# schematic.net
KiCad netlist of a schematic drawn in EAGLE
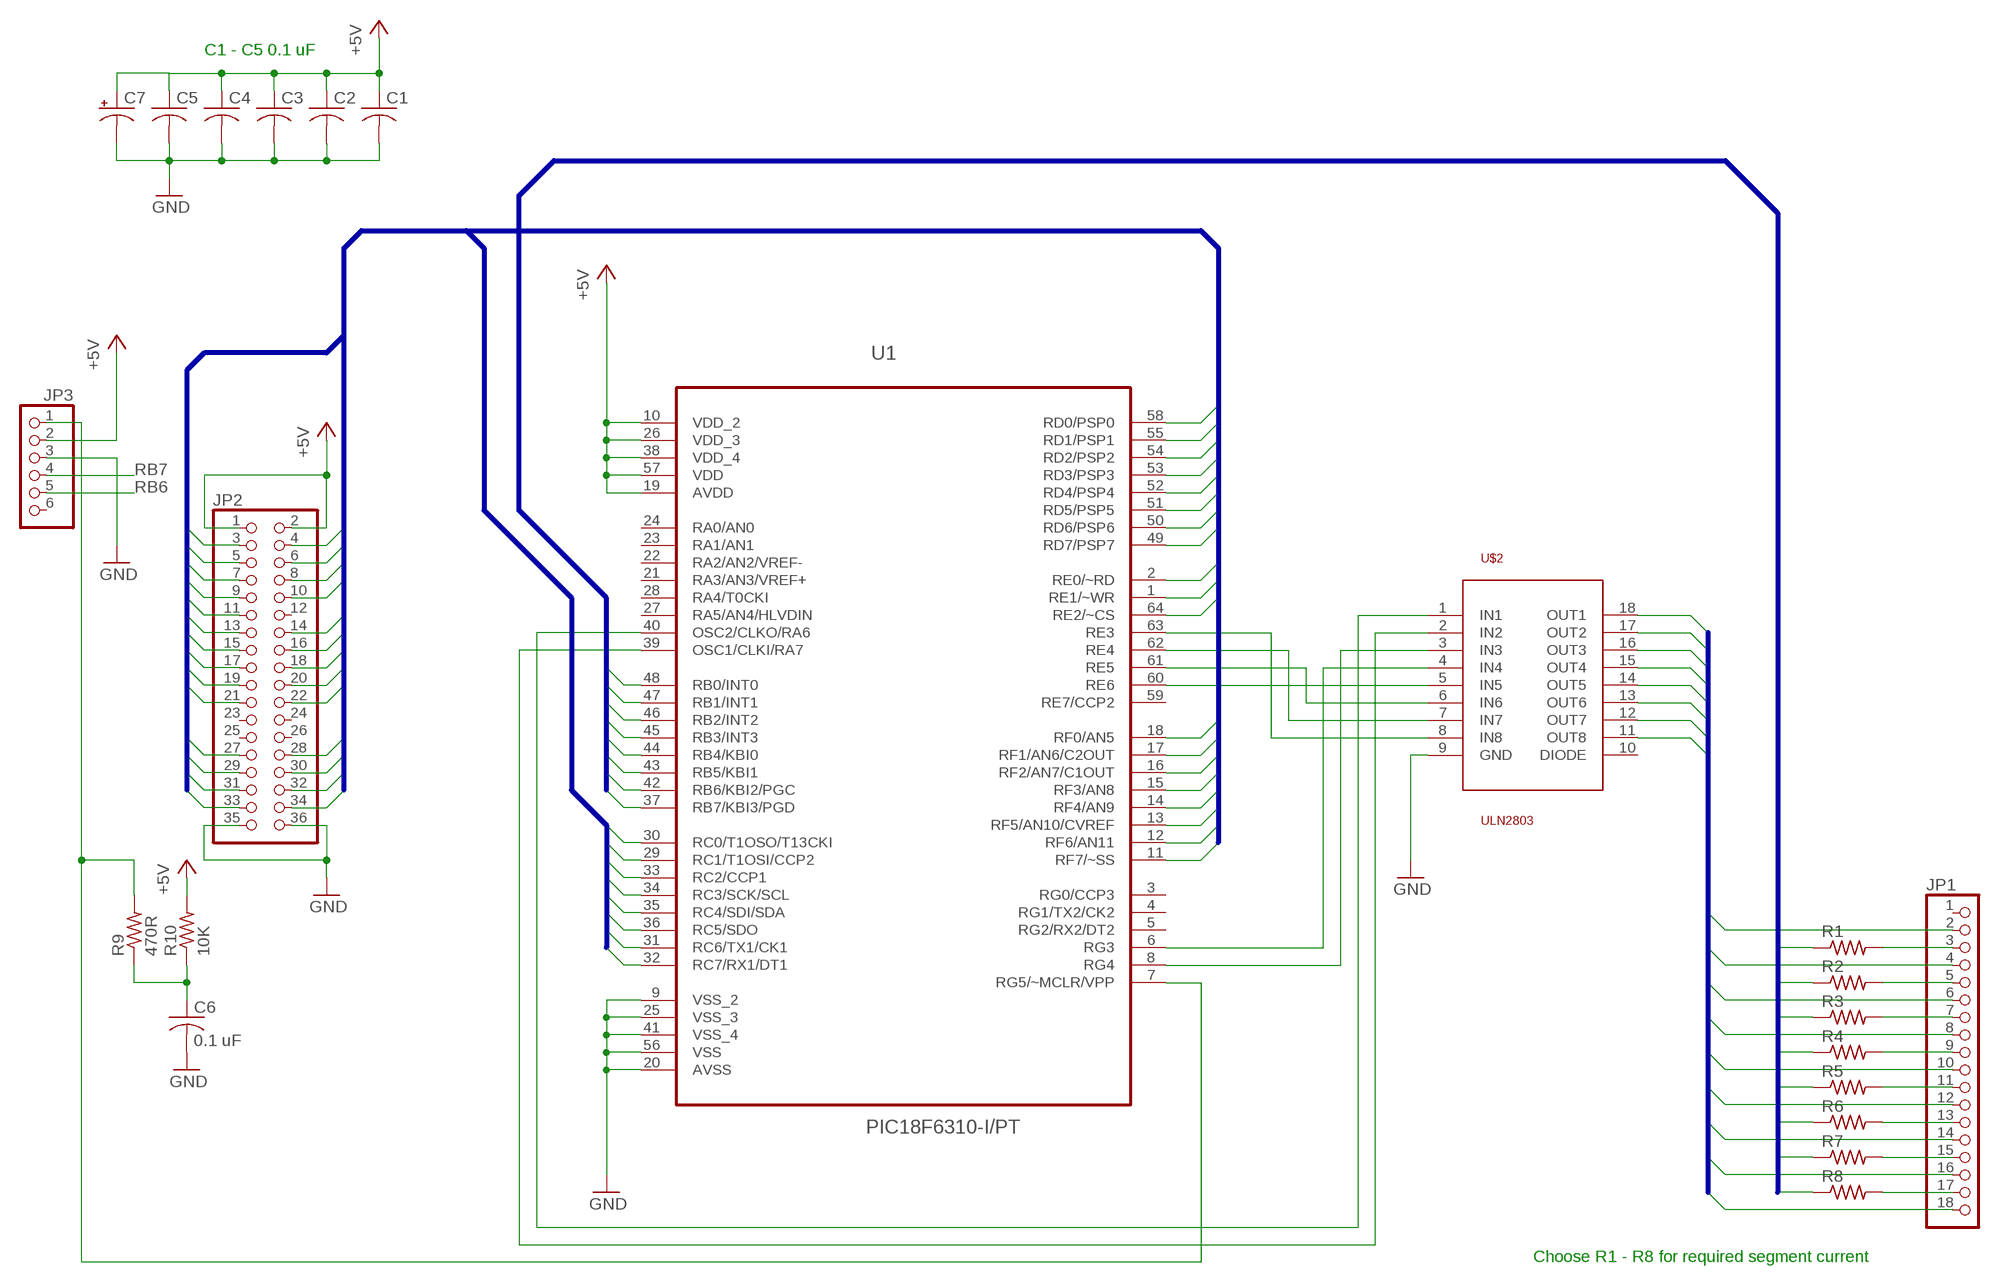
[diagram p0: schematic, sheet 1]

(export (version "E")
  (design (tool "Eeschema 10.0.6"))
  (components
    (comp (ref "C1")
      (value "C-USC0603K")
      (footprint "eagle-import:C0603K")
      (libsource (lib "eagle-import") (part "C-USC0603K"))
    )
    (comp (ref "C2")
      (value "C-USC0603K")
      (footprint "eagle-import:C0603K")
      (libsource (lib "eagle-import") (part "C-USC0603K"))
    )
    (comp (ref "C3")
      (value "C-USC0603K")
      (footprint "eagle-import:C0603K")
      (libsource (lib "eagle-import") (part "C-USC0603K"))
    )
    (comp (ref "C4")
      (value "C-USC0603K")
      (footprint "eagle-import:C0603K")
      (libsource (lib "eagle-import") (part "C-USC0603K"))
    )
    (comp (ref "C5")
      (value "C-USC0603K")
      (footprint "eagle-import:C0603K")
      (libsource (lib "eagle-import") (part "C-USC0603K"))
    )
    (comp (ref "C6")
      (value "0.1 uF")
      (footprint "eagle-import:C0603K")
      (libsource (lib "eagle-import") (part "C-USC0603K"))
    )
    (comp (ref "C7")
      (value "CPOL-USB/3528-21W")
      (footprint "eagle-import:B_3528-21W")
      (libsource (lib "eagle-import") (part "CPOL-USB/3528-21W"))
    )
    (comp (ref "JP1")
      (value "PINHD-1X18")
      (footprint "eagle-import:1X18")
      (libsource (lib "eagle-import") (part "PINHD-1X18"))
    )
    (comp (ref "JP2")
      (value "PINHD-2X18")
      (footprint "eagle-import:2X18")
      (libsource (lib "eagle-import") (part "PINHD-2X18"))
    )
    (comp (ref "JP3")
      (value "PINHD-1X6")
      (footprint "eagle-import:1X06")
      (libsource (lib "eagle-import") (part "PINHD-1X6"))
    )
    (comp (ref "R1")
      (value "R-US_R0603")
      (footprint "eagle-import:R0603")
      (libsource (lib "eagle-import") (part "R-US_R0603"))
    )
    (comp (ref "R2")
      (value "R-US_R0603")
      (footprint "eagle-import:R0603")
      (libsource (lib "eagle-import") (part "R-US_R0603"))
    )
    (comp (ref "R3")
      (value "R-US_R0603")
      (footprint "eagle-import:R0603")
      (libsource (lib "eagle-import") (part "R-US_R0603"))
    )
    (comp (ref "R4")
      (value "R-US_R0603")
      (footprint "eagle-import:R0603")
      (libsource (lib "eagle-import") (part "R-US_R0603"))
    )
    (comp (ref "R5")
      (value "R-US_R0603")
      (footprint "eagle-import:R0603")
      (libsource (lib "eagle-import") (part "R-US_R0603"))
    )
    (comp (ref "R6")
      (value "R-US_R0603")
      (footprint "eagle-import:R0603")
      (libsource (lib "eagle-import") (part "R-US_R0603"))
    )
    (comp (ref "R7")
      (value "R-US_R0603")
      (footprint "eagle-import:R0603")
      (libsource (lib "eagle-import") (part "R-US_R0603"))
    )
    (comp (ref "R8")
      (value "R-US_R0603")
      (footprint "eagle-import:R0603")
      (libsource (lib "eagle-import") (part "R-US_R0603"))
    )
    (comp (ref "R9")
      (value "470R")
      (footprint "eagle-import:R0603")
      (libsource (lib "eagle-import") (part "R-US_R0603"))
    )
    (comp (ref "R10")
      (value "10K")
      (footprint "eagle-import:R0603")
      (libsource (lib "eagle-import") (part "R-US_R0603"))
    )
    (comp (ref "U$2")
      (value "ULN2803")
      (footprint "eagle-import:SO18L")
      (libsource (lib "eagle-import") (part "ULN2803"))
    )
    (comp (ref "U1")
      (value "PIC18F6310-I/PT")
      (footprint "eagle-import:QFP50P1200X1200X120-64N")
      (libsource (lib "eagle-import") (part "PIC18F6310-I/PT"))
    )
  )
  (nets
    (net (code "1") (name "+5V") (class "Default")
      (node (ref "C1") (pin "1") (pinfunction "1_1") (pintype "passive"))
      (node (ref "C2") (pin "1") (pinfunction "1_1") (pintype "passive"))
      (node (ref "C3") (pin "1") (pinfunction "1_1") (pintype "passive"))
      (node (ref "C4") (pin "1") (pinfunction "1_1") (pintype "passive"))
      (node (ref "C5") (pin "1") (pinfunction "1_1") (pintype "passive"))
      (node (ref "C7") (pin "+") (pinfunction "+_+") (pintype "passive"))
      (node (ref "JP2") (pin "1") (pinfunction "1_1") (pintype "passive"))
      (node (ref "JP2") (pin "2") (pinfunction "2_2") (pintype "passive"))
      (node (ref "JP3") (pin "2") (pinfunction "2_2") (pintype "passive"))
      (node (ref "R10") (pin "2") (pinfunction "2_2") (pintype "passive"))
      (node (ref "U1") (pin "10") (pinfunction "VDD_2_10") (pintype "power_in"))
      (node (ref "U1") (pin "19") (pinfunction "AVDD_19") (pintype "power_in"))
      (node (ref "U1") (pin "26") (pinfunction "VDD_3_26") (pintype "power_in"))
      (node (ref "U1") (pin "38") (pinfunction "VDD_4_38") (pintype "power_in"))
      (node (ref "U1") (pin "57") (pinfunction "VDD_57") (pintype "power_in"))
    )
    (net (code "2") (name "/DIGIT1") (class "Default")
      (node (ref "JP1") (pin "4") (pinfunction "4_4") (pintype "passive"))
      (node (ref "U$2") (pin "18") (pinfunction "OUT1_18") (pintype "open_collector"))
    )
    (net (code "3") (name "/DIGIT2") (class "Default")
      (node (ref "JP1") (pin "6") (pinfunction "6_6") (pintype "passive"))
      (node (ref "U$2") (pin "17") (pinfunction "OUT2_17") (pintype "open_collector"))
    )
    (net (code "4") (name "/DIGIT3") (class "Default")
      (node (ref "JP1") (pin "8") (pinfunction "8_8") (pintype "passive"))
      (node (ref "U$2") (pin "16") (pinfunction "OUT3_16") (pintype "open_collector"))
    )
    (net (code "5") (name "/DIGIT4") (class "Default")
      (node (ref "JP1") (pin "10") (pinfunction "10_10") (pintype "passive"))
      (node (ref "U$2") (pin "15") (pinfunction "OUT4_15") (pintype "open_collector"))
    )
    (net (code "6") (name "/DIGIT5") (class "Default")
      (node (ref "JP1") (pin "12") (pinfunction "12_12") (pintype "passive"))
      (node (ref "U$2") (pin "14") (pinfunction "OUT5_14") (pintype "open_collector"))
    )
    (net (code "7") (name "/DIGIT6") (class "Default")
      (node (ref "JP1") (pin "14") (pinfunction "14_14") (pintype "passive"))
      (node (ref "U$2") (pin "13") (pinfunction "OUT6_13") (pintype "open_collector"))
    )
    (net (code "8") (name "/DIGIT7") (class "Default")
      (node (ref "JP1") (pin "16") (pinfunction "16_16") (pintype "passive"))
      (node (ref "U$2") (pin "12") (pinfunction "OUT7_12") (pintype "open_collector"))
    )
    (net (code "9") (name "/DIGIT8") (class "Default")
      (node (ref "JP1") (pin "18") (pinfunction "18_18") (pintype "passive"))
      (node (ref "U$2") (pin "11") (pinfunction "OUT8_11") (pintype "open_collector"))
    )
    (net (code "10") (name "/DIODE") (class "Default")
      (node (ref "U$2") (pin "10") (pinfunction "DIODE_10") (pintype "power_in"))
    )
    (net (code "11") (name "/RB0") (class "Default")
      (node (ref "R1") (pin "1") (pinfunction "1_1") (pintype "passive"))
      (node (ref "U1") (pin "48") (pinfunction "RB0/INT0_48") (pintype "bidirectional"))
    )
    (net (code "12") (name "/RB1") (class "Default")
      (node (ref "R2") (pin "1") (pinfunction "1_1") (pintype "passive"))
      (node (ref "U1") (pin "47") (pinfunction "RB1/INT1_47") (pintype "bidirectional"))
    )
    (net (code "13") (name "/RB2") (class "Default")
      (node (ref "R3") (pin "1") (pinfunction "1_1") (pintype "passive"))
      (node (ref "U1") (pin "46") (pinfunction "RB2/INT2_46") (pintype "bidirectional"))
    )
    (net (code "14") (name "/RB3") (class "Default")
      (node (ref "R4") (pin "1") (pinfunction "1_1") (pintype "passive"))
      (node (ref "U1") (pin "45") (pinfunction "RB3/INT3_45") (pintype "bidirectional"))
    )
    (net (code "15") (name "/RB4") (class "Default")
      (node (ref "R5") (pin "1") (pinfunction "1_1") (pintype "passive"))
      (node (ref "U1") (pin "44") (pinfunction "RB4/KBI0_44") (pintype "bidirectional"))
    )
    (net (code "16") (name "/RB5") (class "Default")
      (node (ref "R6") (pin "1") (pinfunction "1_1") (pintype "passive"))
      (node (ref "U1") (pin "43") (pinfunction "RB5/KBI1_43") (pintype "bidirectional"))
    )
    (net (code "17") (name "/RB6") (class "Default")
      (node (ref "JP3") (pin "5") (pinfunction "5_5") (pintype "passive"))
      (node (ref "R7") (pin "1") (pinfunction "1_1") (pintype "passive"))
      (node (ref "U1") (pin "42") (pinfunction "RB6/KBI2/PGC_42") (pintype "bidirectional"))
    )
    (net (code "18") (name "/RB7") (class "Default")
      (node (ref "JP3") (pin "4") (pinfunction "4_4") (pintype "passive"))
      (node (ref "R8") (pin "1") (pinfunction "1_1") (pintype "passive"))
      (node (ref "U1") (pin "37") (pinfunction "RB7/KBI3/PGD_37") (pintype "bidirectional"))
    )
    (net (code "19") (name "/RC0") (class "Default")
      (node (ref "JP2") (pin "27") (pinfunction "27_27") (pintype "passive"))
      (node (ref "U1") (pin "30") (pinfunction "RC0/T1OSO/T13CKI_30") (pintype "bidirectional"))
    )
    (net (code "20") (name "/RC1") (class "Default")
      (node (ref "JP2") (pin "28") (pinfunction "28_28") (pintype "passive"))
      (node (ref "U1") (pin "29") (pinfunction "RC1/T1OSI/CCP2_29") (pintype "bidirectional"))
    )
    (net (code "21") (name "/RC2") (class "Default")
      (node (ref "JP2") (pin "29") (pinfunction "29_29") (pintype "passive"))
      (node (ref "U1") (pin "33") (pinfunction "RC2/CCP1_33") (pintype "bidirectional"))
    )
    (net (code "22") (name "/RC3") (class "Default")
      (node (ref "JP2") (pin "30") (pinfunction "30_30") (pintype "passive"))
      (node (ref "U1") (pin "34") (pinfunction "RC3/SCK/SCL_34") (pintype "bidirectional"))
    )
    (net (code "23") (name "/RC4") (class "Default")
      (node (ref "JP2") (pin "31") (pinfunction "31_31") (pintype "passive"))
      (node (ref "U1") (pin "35") (pinfunction "RC4/SDI/SDA_35") (pintype "bidirectional"))
    )
    (net (code "24") (name "/RC5") (class "Default")
      (node (ref "JP2") (pin "32") (pinfunction "32_32") (pintype "passive"))
      (node (ref "U1") (pin "36") (pinfunction "RC5/SDO_36") (pintype "bidirectional"))
    )
    (net (code "25") (name "/RC6") (class "Default")
      (node (ref "JP2") (pin "33") (pinfunction "33_33") (pintype "passive"))
      (node (ref "U1") (pin "31") (pinfunction "RC6/TX1/CK1_31") (pintype "bidirectional"))
    )
    (net (code "26") (name "/RC7") (class "Default")
      (node (ref "JP2") (pin "34") (pinfunction "34_34") (pintype "passive"))
      (node (ref "U1") (pin "32") (pinfunction "RC7/RX1/DT1_32") (pintype "bidirectional"))
    )
    (net (code "27") (name "/RD0") (class "Default")
      (node (ref "JP2") (pin "3") (pinfunction "3_3") (pintype "passive"))
      (node (ref "U1") (pin "58") (pinfunction "RD0/PSP0_58") (pintype "bidirectional"))
    )
    (net (code "28") (name "/RD1") (class "Default")
      (node (ref "JP2") (pin "4") (pinfunction "4_4") (pintype "passive"))
      (node (ref "U1") (pin "55") (pinfunction "RD1/PSP1_55") (pintype "bidirectional"))
    )
    (net (code "29") (name "/RD2") (class "Default")
      (node (ref "JP2") (pin "5") (pinfunction "5_5") (pintype "passive"))
      (node (ref "U1") (pin "54") (pinfunction "RD2/PSP2_54") (pintype "bidirectional"))
    )
    (net (code "30") (name "/RD3") (class "Default")
      (node (ref "JP2") (pin "6") (pinfunction "6_6") (pintype "passive"))
      (node (ref "U1") (pin "53") (pinfunction "RD3/PSP3_53") (pintype "bidirectional"))
    )
    (net (code "31") (name "/RD4") (class "Default")
      (node (ref "JP2") (pin "7") (pinfunction "7_7") (pintype "passive"))
      (node (ref "U1") (pin "52") (pinfunction "RD4/PSP4_52") (pintype "bidirectional"))
    )
    (net (code "32") (name "/RD5") (class "Default")
      (node (ref "JP2") (pin "8") (pinfunction "8_8") (pintype "passive"))
      (node (ref "U1") (pin "51") (pinfunction "RD5/PSP5_51") (pintype "bidirectional"))
    )
    (net (code "33") (name "/RD6") (class "Default")
      (node (ref "JP2") (pin "9") (pinfunction "9_9") (pintype "passive"))
      (node (ref "U1") (pin "50") (pinfunction "RD6/PSP6_50") (pintype "bidirectional"))
    )
    (net (code "34") (name "/RD7") (class "Default")
      (node (ref "JP2") (pin "10") (pinfunction "10_10") (pintype "passive"))
      (node (ref "U1") (pin "49") (pinfunction "RD7/PSP7_49") (pintype "bidirectional"))
    )
    (net (code "35") (name "/RE0") (class "Default")
      (node (ref "JP2") (pin "13") (pinfunction "13_13") (pintype "passive"))
      (node (ref "U1") (pin "2") (pinfunction "RE0/~{RD}_2") (pintype "bidirectional"))
    )
    (net (code "36") (name "/RE1") (class "Default")
      (node (ref "JP2") (pin "14") (pinfunction "14_14") (pintype "passive"))
      (node (ref "U1") (pin "1") (pinfunction "RE1/~{WR}_1") (pintype "bidirectional"))
    )
    (net (code "37") (name "/RE2") (class "Default")
      (node (ref "JP2") (pin "11") (pinfunction "11_11") (pintype "passive"))
      (node (ref "U1") (pin "64") (pinfunction "RE2/~{CS}_64") (pintype "bidirectional"))
    )
    (net (code "38") (name "/RF0") (class "Default")
      (node (ref "JP2") (pin "15") (pinfunction "15_15") (pintype "passive"))
      (node (ref "U1") (pin "18") (pinfunction "RF0/AN5_18") (pintype "bidirectional"))
    )
    (net (code "39") (name "/RF1") (class "Default")
      (node (ref "JP2") (pin "16") (pinfunction "16_16") (pintype "passive"))
      (node (ref "U1") (pin "17") (pinfunction "RF1/AN6/C2OUT_17") (pintype "bidirectional"))
    )
    (net (code "40") (name "/RF2") (class "Default")
      (node (ref "JP2") (pin "17") (pinfunction "17_17") (pintype "passive"))
      (node (ref "U1") (pin "16") (pinfunction "RF2/AN7/C1OUT_16") (pintype "bidirectional"))
    )
    (net (code "41") (name "/RF3") (class "Default")
      (node (ref "JP2") (pin "18") (pinfunction "18_18") (pintype "passive"))
      (node (ref "U1") (pin "15") (pinfunction "RF3/AN8_15") (pintype "bidirectional"))
    )
    (net (code "42") (name "/RF4") (class "Default")
      (node (ref "JP2") (pin "19") (pinfunction "19_19") (pintype "passive"))
      (node (ref "U1") (pin "14") (pinfunction "RF4/AN9_14") (pintype "bidirectional"))
    )
    (net (code "43") (name "/RF5") (class "Default")
      (node (ref "JP2") (pin "20") (pinfunction "20_20") (pintype "passive"))
      (node (ref "U1") (pin "13") (pinfunction "RF5/AN10/CVREF_13") (pintype "bidirectional"))
    )
    (net (code "44") (name "/RF6") (class "Default")
      (node (ref "JP2") (pin "21") (pinfunction "21_21") (pintype "passive"))
      (node (ref "U1") (pin "12") (pinfunction "RF6/AN11_12") (pintype "bidirectional"))
    )
    (net (code "45") (name "/RF7") (class "Default")
      (node (ref "JP2") (pin "22") (pinfunction "22_22") (pintype "passive"))
      (node (ref "U1") (pin "11") (pinfunction "RF7/~{SS}_11") (pintype "bidirectional"))
    )
    (net (code "46") (name "GND") (class "Default")
      (node (ref "C1") (pin "2") (pinfunction "2_2") (pintype "passive"))
      (node (ref "C2") (pin "2") (pinfunction "2_2") (pintype "passive"))
      (node (ref "C3") (pin "2") (pinfunction "2_2") (pintype "passive"))
      (node (ref "C4") (pin "2") (pinfunction "2_2") (pintype "passive"))
      (node (ref "C5") (pin "2") (pinfunction "2_2") (pintype "passive"))
      (node (ref "C6") (pin "2") (pinfunction "2_2") (pintype "passive"))
      (node (ref "C7") (pin "-") (pinfunction "-_-") (pintype "passive"))
      (node (ref "JP2") (pin "35") (pinfunction "35_35") (pintype "passive"))
      (node (ref "JP2") (pin "36") (pinfunction "36_36") (pintype "passive"))
      (node (ref "JP3") (pin "3") (pinfunction "3_3") (pintype "passive"))
      (node (ref "U$2") (pin "9") (pinfunction "GND_9") (pintype "power_in"))
      (node (ref "U1") (pin "20") (pinfunction "AVSS_20") (pintype "power_in"))
      (node (ref "U1") (pin "25") (pinfunction "VSS_3_25") (pintype "power_in"))
      (node (ref "U1") (pin "41") (pinfunction "VSS_4_41") (pintype "power_in"))
      (node (ref "U1") (pin "56") (pinfunction "VSS_56") (pintype "power_in"))
      (node (ref "U1") (pin "9") (pinfunction "VSS_2_9") (pintype "power_in"))
    )
    (net (code "47") (name "Net-(C6-Pad1)") (class "Default")
      (node (ref "C6") (pin "1") (pinfunction "1_1") (pintype "passive"))
      (node (ref "R10") (pin "1") (pinfunction "1_1") (pintype "passive"))
      (node (ref "R9") (pin "1") (pinfunction "1_1") (pintype "passive"))
    )
    (net (code "48") (name "Net-(JP1-Pad3)") (class "Default")
      (node (ref "JP1") (pin "3") (pinfunction "3_3") (pintype "passive"))
      (node (ref "R1") (pin "2") (pinfunction "2_2") (pintype "passive"))
    )
    (net (code "49") (name "Net-(JP1-Pad5)") (class "Default")
      (node (ref "JP1") (pin "5") (pinfunction "5_5") (pintype "passive"))
      (node (ref "R2") (pin "2") (pinfunction "2_2") (pintype "passive"))
    )
    (net (code "50") (name "Net-(JP1-Pad7)") (class "Default")
      (node (ref "JP1") (pin "7") (pinfunction "7_7") (pintype "passive"))
      (node (ref "R3") (pin "2") (pinfunction "2_2") (pintype "passive"))
    )
    (net (code "51") (name "Net-(JP1-Pad9)") (class "Default")
      (node (ref "JP1") (pin "9") (pinfunction "9_9") (pintype "passive"))
      (node (ref "R4") (pin "2") (pinfunction "2_2") (pintype "passive"))
    )
    (net (code "52") (name "Net-(JP1-Pad11)") (class "Default")
      (node (ref "JP1") (pin "11") (pinfunction "11_11") (pintype "passive"))
      (node (ref "R5") (pin "2") (pinfunction "2_2") (pintype "passive"))
    )
    (net (code "53") (name "Net-(JP1-Pad13)") (class "Default")
      (node (ref "JP1") (pin "13") (pinfunction "13_13") (pintype "passive"))
      (node (ref "R6") (pin "2") (pinfunction "2_2") (pintype "passive"))
    )
    (net (code "54") (name "Net-(JP1-Pad15)") (class "Default")
      (node (ref "JP1") (pin "15") (pinfunction "15_15") (pintype "passive"))
      (node (ref "R7") (pin "2") (pinfunction "2_2") (pintype "passive"))
    )
    (net (code "55") (name "Net-(JP1-Pad17)") (class "Default")
      (node (ref "JP1") (pin "17") (pinfunction "17_17") (pintype "passive"))
      (node (ref "R8") (pin "2") (pinfunction "2_2") (pintype "passive"))
    )
    (net (code "56") (name "Net-(U$2-IN1)") (class "Default")
      (node (ref "U$2") (pin "1") (pinfunction "IN1_1") (pintype "input"))
      (node (ref "U1") (pin "40") (pinfunction "OSC2/CLKO/RA6_40") (pintype "bidirectional"))
    )
    (net (code "57") (name "Net-(U$2-IN2)") (class "Default")
      (node (ref "U$2") (pin "2") (pinfunction "IN2_2") (pintype "input"))
      (node (ref "U1") (pin "39") (pinfunction "OSC1/CLKI/RA7_39") (pintype "bidirectional"))
    )
    (net (code "58") (name "Net-(U$2-IN3)") (class "Default")
      (node (ref "U$2") (pin "3") (pinfunction "IN3_3") (pintype "input"))
      (node (ref "U1") (pin "8") (pinfunction "RG4_8") (pintype "bidirectional"))
    )
    (net (code "59") (name "Net-(U$2-IN4)") (class "Default")
      (node (ref "U$2") (pin "4") (pinfunction "IN4_4") (pintype "input"))
      (node (ref "U1") (pin "6") (pinfunction "RG3_6") (pintype "bidirectional"))
    )
    (net (code "60") (name "Net-(U$2-IN5)") (class "Default")
      (node (ref "U$2") (pin "5") (pinfunction "IN5_5") (pintype "input"))
      (node (ref "U1") (pin "60") (pinfunction "RE6_60") (pintype "bidirectional"))
    )
    (net (code "61") (name "Net-(U$2-IN6)") (class "Default")
      (node (ref "U$2") (pin "6") (pinfunction "IN6_6") (pintype "input"))
      (node (ref "U1") (pin "61") (pinfunction "RE5_61") (pintype "bidirectional"))
    )
    (net (code "62") (name "Net-(U$2-IN7)") (class "Default")
      (node (ref "U$2") (pin "7") (pinfunction "IN7_7") (pintype "input"))
      (node (ref "U1") (pin "62") (pinfunction "RE4_62") (pintype "bidirectional"))
    )
    (net (code "63") (name "Net-(U$2-IN8)") (class "Default")
      (node (ref "U$2") (pin "8") (pinfunction "IN8_8") (pintype "input"))
      (node (ref "U1") (pin "63") (pinfunction "RE3_63") (pintype "bidirectional"))
    )
    (net (code "64") (name "Net-(U1-RG5{slash}~{MCLR{slash}VPP})") (class "Default")
      (node (ref "JP3") (pin "1") (pinfunction "1_1") (pintype "passive"))
      (node (ref "R9") (pin "2") (pinfunction "2_2") (pintype "passive"))
      (node (ref "U1") (pin "7") (pinfunction "RG5/~{MCLR/VPP}_7") (pintype "bidirectional"))
    )
    (net (code "65") (name "unconnected-(JP1-Pad1)") (class "Default")
      (node (ref "JP1") (pin "1") (pinfunction "1_1") (pintype "passive"))
    )
    (net (code "66") (name "unconnected-(JP1-Pad2)") (class "Default")
      (node (ref "JP1") (pin "2") (pinfunction "2_2") (pintype "passive"))
    )
    (net (code "67") (name "unconnected-(JP2-Pad12)") (class "Default")
      (node (ref "JP2") (pin "12") (pinfunction "12_12") (pintype "passive"))
    )
    (net (code "68") (name "unconnected-(JP2-Pad23)") (class "Default")
      (node (ref "JP2") (pin "23") (pinfunction "23_23") (pintype "passive"))
    )
    (net (code "69") (name "unconnected-(JP2-Pad24)") (class "Default")
      (node (ref "JP2") (pin "24") (pinfunction "24_24") (pintype "passive"))
    )
    (net (code "70") (name "unconnected-(JP2-Pad25)") (class "Default")
      (node (ref "JP2") (pin "25") (pinfunction "25_25") (pintype "passive"))
    )
    (net (code "71") (name "unconnected-(JP2-Pad26)") (class "Default")
      (node (ref "JP2") (pin "26") (pinfunction "26_26") (pintype "passive"))
    )
    (net (code "72") (name "unconnected-(JP3-Pad6)") (class "Default")
      (node (ref "JP3") (pin "6") (pinfunction "6_6") (pintype "passive"))
    )
    (net (code "73") (name "unconnected-(U1-RA0{slash}AN0-Pad24)") (class "Default")
      (node (ref "U1") (pin "24") (pinfunction "RA0/AN0_24") (pintype "bidirectional"))
    )
    (net (code "74") (name "unconnected-(U1-RA1{slash}AN1-Pad23)") (class "Default")
      (node (ref "U1") (pin "23") (pinfunction "RA1/AN1_23") (pintype "bidirectional"))
    )
    (net (code "75") (name "unconnected-(U1-RA2{slash}AN2{slash}VREF--Pad22)") (class "Default")
      (node (ref "U1") (pin "22") (pinfunction "RA2/AN2/VREF-_22") (pintype "bidirectional"))
    )
    (net (code "76") (name "unconnected-(U1-RA3{slash}AN3{slash}VREF+-Pad21)") (class "Default")
      (node (ref "U1") (pin "21") (pinfunction "RA3/AN3/VREF+_21") (pintype "bidirectional"))
    )
    (net (code "77") (name "unconnected-(U1-RA4{slash}T0CKI-Pad28)") (class "Default")
      (node (ref "U1") (pin "28") (pinfunction "RA4/T0CKI_28") (pintype "bidirectional"))
    )
    (net (code "78") (name "unconnected-(U1-RA5{slash}AN4{slash}HLVDIN-Pad27)") (class "Default")
      (node (ref "U1") (pin "27") (pinfunction "RA5/AN4/HLVDIN_27") (pintype "bidirectional"))
    )
    (net (code "79") (name "unconnected-(U1-RE7{slash}CCP2-Pad59)") (class "Default")
      (node (ref "U1") (pin "59") (pinfunction "RE7/CCP2_59") (pintype "bidirectional"))
    )
    (net (code "80") (name "unconnected-(U1-RG0{slash}CCP3-Pad3)") (class "Default")
      (node (ref "U1") (pin "3") (pinfunction "RG0/CCP3_3") (pintype "bidirectional"))
    )
    (net (code "81") (name "unconnected-(U1-RG1{slash}TX2{slash}CK2-Pad4)") (class "Default")
      (node (ref "U1") (pin "4") (pinfunction "RG1/TX2/CK2_4") (pintype "bidirectional"))
    )
    (net (code "82") (name "unconnected-(U1-RG2{slash}RX2{slash}DT2-Pad5)") (class "Default")
      (node (ref "U1") (pin "5") (pinfunction "RG2/RX2/DT2_5") (pintype "bidirectional"))
    )
  )
)
